# drive.net
KiCad netlist of a schematic drawn in EAGLE
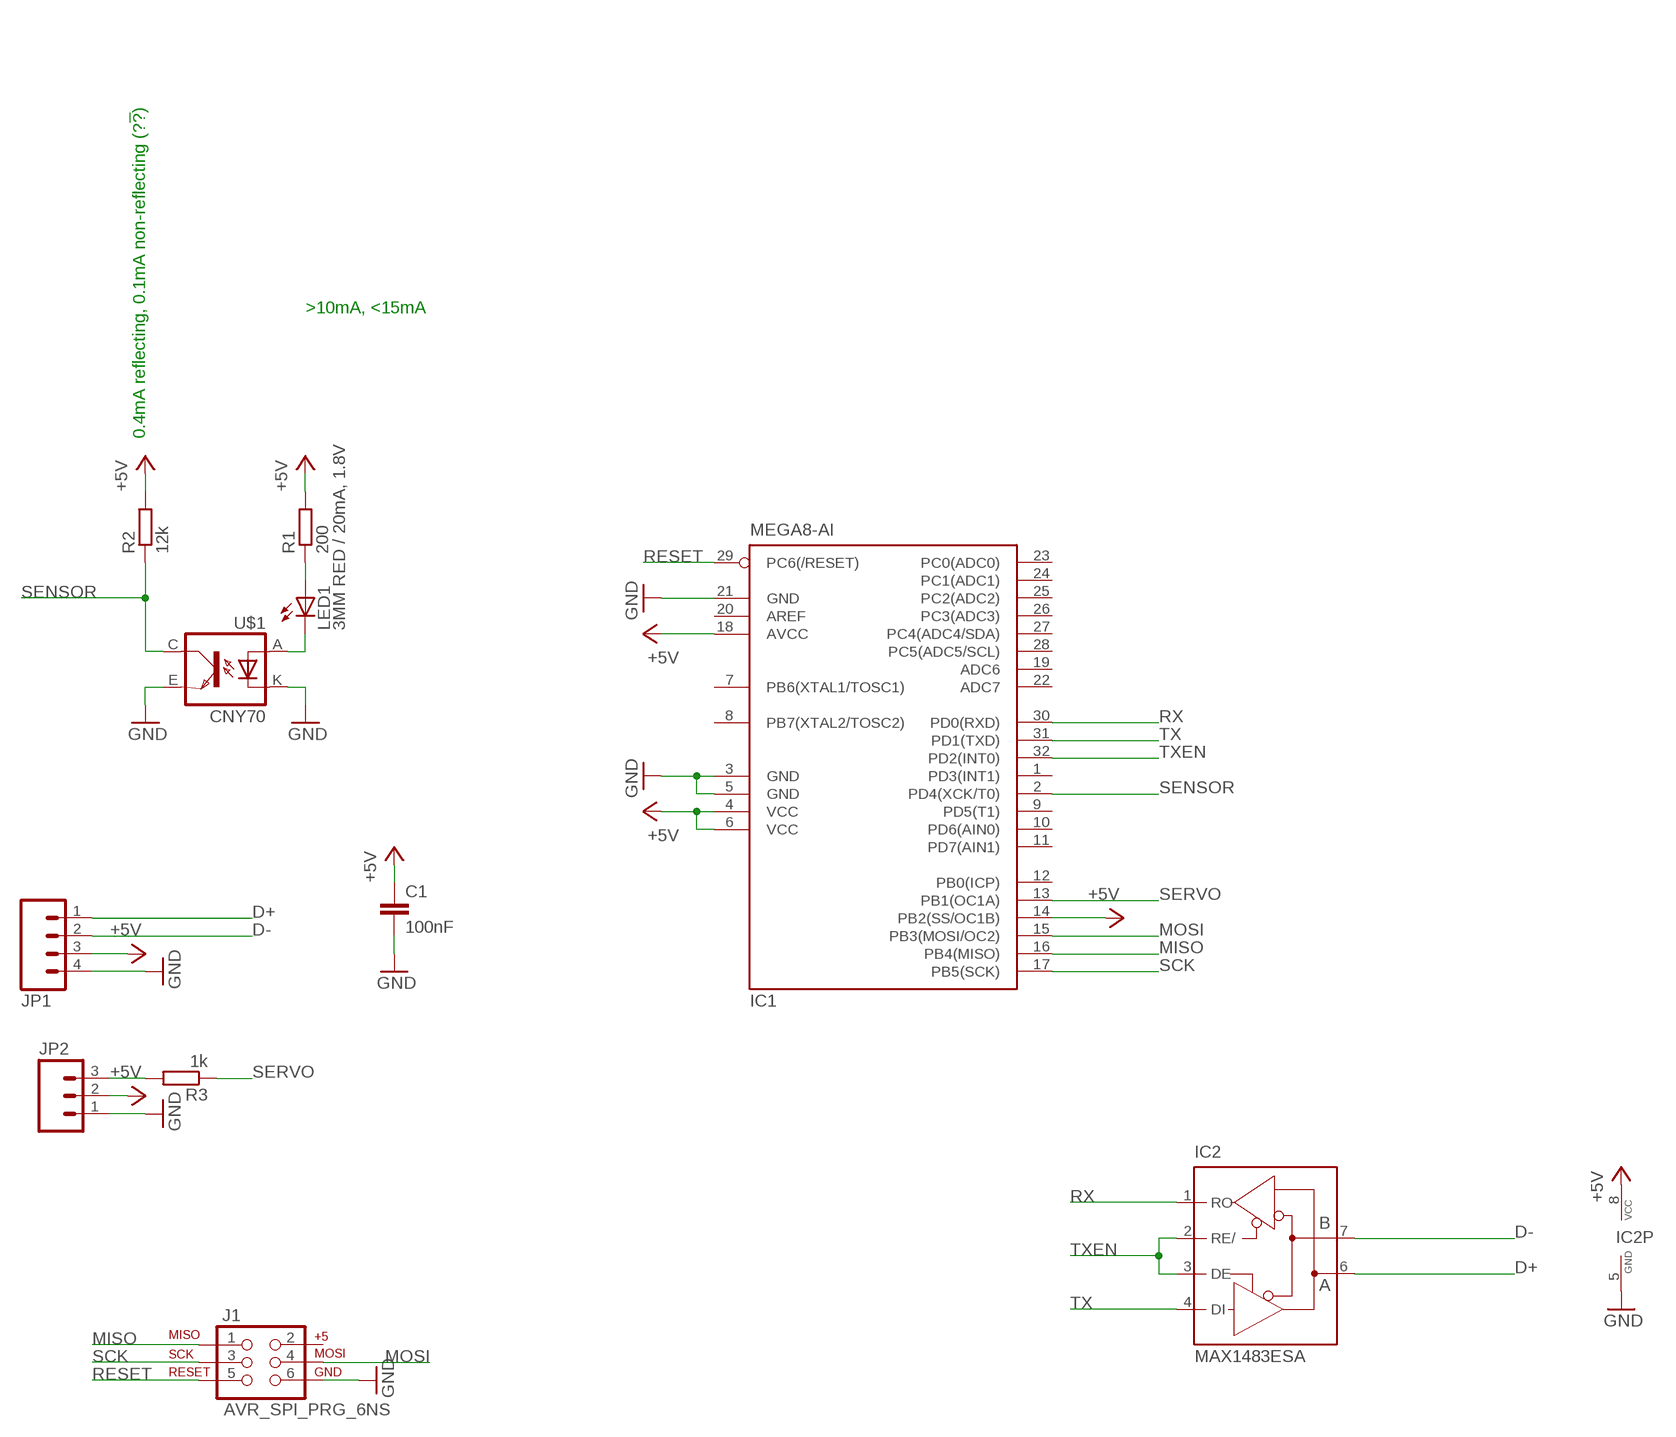
[diagram p0: schematic, sheet 1]

(export (version "E")
  (design (tool "Eeschema 10.0.6"))
  (components
    (comp (ref "C1")
      (value "100nF")
      (footprint "eagle-import:C0805")
      (libsource (lib "eagle-import") (part "C-EUC0805"))
    )
    (comp (ref "IC1")
      (value "MEGA8-AI")
      (footprint "eagle-import:TQFP32-08")
      (fields (field (name "MPN") "ATMEGA8-16AU"))
      (libsource (lib "eagle-import") (part "MEGA8-AI"))
    )
    (comp (ref "IC2")
      (value "MAX1483ESA")
      (footprint "eagle-import:SO08")
      (fields (field (name "MF") "MAXIM") (field (name "MPN") "MAX481CSA"))
      (libsource (lib "eagle-import") (part "MAX481CSA"))
    )
    (comp (ref "J1")
      (value "AVR_SPI_PRG_6NS")
      (footprint "eagle-import:2X3-NS")
      (libsource (lib "eagle-import") (part "AVR_SPI_PRG_6NS"))
    )
    (comp (ref "JP1")
      (value "M04POLAR")
      (footprint "eagle-import:MOLEX-1X4")
      (libsource (lib "eagle-import") (part "M04POLAR"))
    )
    (comp (ref "JP2")
      (value "M03PTH")
      (footprint "eagle-import:1X03")
      (libsource (lib "eagle-import") (part "M03PTH"))
    )
    (comp (ref "LED1")
      (value "3MM RED / 20mA, 1.8V")
      (footprint "eagle-import:LED3MM")
      (libsource (lib "eagle-import") (part "LED3MM"))
    )
    (comp (ref "R1")
      (value "200")
      (footprint "eagle-import:R0805")
      (libsource (lib "eagle-import") (part "R-EU_R0805"))
    )
    (comp (ref "R2")
      (value "12k")
      (footprint "eagle-import:R0805")
      (libsource (lib "eagle-import") (part "R-EU_R0805"))
    )
    (comp (ref "R3")
      (value "1k")
      (footprint "eagle-import:R0805")
      (libsource (lib "eagle-import") (part "R-EU_R0805"))
    )
    (comp (ref "U$1")
      (value "CNY70")
      (footprint "eagle-import:4")
      (libsource (lib "eagle-import") (part "CNY70"))
    )
  )
  (nets
    (net (code "1") (name "+5V") (class "Default")
      (node (ref "C1") (pin "1") (pinfunction "1_1") (pintype "passive"))
      (node (ref "IC1") (pin "14") (pinfunction "PB2(SS/OC1B)_14") (pintype "bidirectional"))
      (node (ref "IC1") (pin "18") (pinfunction "AVCC_18") (pintype "power_in"))
      (node (ref "IC1") (pin "4") (pinfunction "VCC_4") (pintype "power_in"))
      (node (ref "IC1") (pin "6") (pinfunction "VCC_6") (pintype "power_in"))
      (node (ref "IC2") (pin "8") (pinfunction "VCC_8") (pintype "power_in"))
      (node (ref "JP1") (pin "3") (pinfunction "3_3") (pintype "passive"))
      (node (ref "JP2") (pin "2") (pinfunction "2_2") (pintype "passive"))
      (node (ref "R1") (pin "2") (pinfunction "2_2") (pintype "passive"))
      (node (ref "R2") (pin "2") (pinfunction "2_2") (pintype "passive"))
    )
    (net (code "2") (name "/D+") (class "Default")
      (node (ref "IC2") (pin "6") (pinfunction "A_6") (pintype "passive"))
      (node (ref "JP1") (pin "1") (pinfunction "1_1") (pintype "passive"))
    )
    (net (code "3") (name "/D-") (class "Default")
      (node (ref "IC2") (pin "7") (pinfunction "B_7") (pintype "passive"))
      (node (ref "JP1") (pin "2") (pinfunction "2_2") (pintype "passive"))
    )
    (net (code "4") (name "/MISO") (class "Default")
      (node (ref "IC1") (pin "16") (pinfunction "PB4(MISO)_16") (pintype "bidirectional"))
      (node (ref "J1") (pin "1") (pinfunction "1_1") (pintype "passive"))
    )
    (net (code "5") (name "/MOSI") (class "Default")
      (node (ref "IC1") (pin "15") (pinfunction "PB3(MOSI/OC2)_15") (pintype "bidirectional"))
      (node (ref "J1") (pin "4") (pinfunction "4_4") (pintype "passive"))
    )
    (net (code "6") (name "/RESET") (class "Default")
      (node (ref "IC1") (pin "29") (pinfunction "PC6(/RESET)_29") (pintype "bidirectional"))
      (node (ref "J1") (pin "5") (pinfunction "5_5") (pintype "passive"))
    )
    (net (code "7") (name "/RX") (class "Default")
      (node (ref "IC1") (pin "30") (pinfunction "PD0(RXD)_30") (pintype "bidirectional"))
      (node (ref "IC2") (pin "1") (pinfunction "RO_1") (pintype "output"))
    )
    (net (code "8") (name "/SCK") (class "Default")
      (node (ref "IC1") (pin "17") (pinfunction "PB5(SCK)_17") (pintype "bidirectional"))
      (node (ref "J1") (pin "3") (pinfunction "3_3") (pintype "passive"))
    )
    (net (code "9") (name "/SENSOR") (class "Default")
      (node (ref "IC1") (pin "2") (pinfunction "PD4(XCK/T0)_2") (pintype "bidirectional"))
      (node (ref "R2") (pin "1") (pinfunction "1_1") (pintype "passive"))
      (node (ref "U$1") (pin "C") (pinfunction "COL_C") (pintype "passive"))
    )
    (net (code "10") (name "/SERVO") (class "Default")
      (node (ref "IC1") (pin "13") (pinfunction "PB1(OC1A)_13") (pintype "bidirectional"))
      (node (ref "R3") (pin "1") (pinfunction "1_1") (pintype "passive"))
    )
    (net (code "11") (name "/TX") (class "Default")
      (node (ref "IC1") (pin "31") (pinfunction "PD1(TXD)_31") (pintype "bidirectional"))
      (node (ref "IC2") (pin "4") (pinfunction "DI_4") (pintype "input"))
    )
    (net (code "12") (name "/TXEN") (class "Default")
      (node (ref "IC1") (pin "32") (pinfunction "PD2(INT0)_32") (pintype "bidirectional"))
      (node (ref "IC2") (pin "2") (pinfunction "RE/_2") (pintype "input"))
      (node (ref "IC2") (pin "3") (pinfunction "DE_3") (pintype "input"))
    )
    (net (code "13") (name "GND") (class "Default")
      (node (ref "C1") (pin "2") (pinfunction "2_2") (pintype "passive"))
      (node (ref "IC1") (pin "21") (pinfunction "GND_21") (pintype "power_in"))
      (node (ref "IC1") (pin "3") (pinfunction "GND_3") (pintype "power_in"))
      (node (ref "IC1") (pin "5") (pinfunction "GND_5") (pintype "power_in"))
      (node (ref "IC2") (pin "5") (pinfunction "GND_5") (pintype "power_in"))
      (node (ref "J1") (pin "6") (pinfunction "6_6") (pintype "passive"))
      (node (ref "JP1") (pin "4") (pinfunction "4_4") (pintype "passive"))
      (node (ref "JP2") (pin "1") (pinfunction "1_1") (pintype "passive"))
      (node (ref "U$1") (pin "E") (pinfunction "EMI_E") (pintype "passive"))
      (node (ref "U$1") (pin "K") (pinfunction "C_K") (pintype "passive"))
    )
    (net (code "14") (name "Net-(JP2-Pad3)") (class "Default")
      (node (ref "JP2") (pin "3") (pinfunction "3_3") (pintype "passive"))
      (node (ref "R3") (pin "2") (pinfunction "2_2") (pintype "passive"))
    )
    (net (code "15") (name "Net-(LED1-C)") (class "Default")
      (node (ref "LED1") (pin "K") (pinfunction "C_K") (pintype "passive"))
      (node (ref "U$1") (pin "A") (pinfunction "A_A") (pintype "passive"))
    )
    (net (code "16") (name "Net-(LED1-PadA)") (class "Default")
      (node (ref "LED1") (pin "A") (pinfunction "A_A") (pintype "passive"))
      (node (ref "R1") (pin "1") (pinfunction "1_1") (pintype "passive"))
    )
    (net (code "17") (name "unconnected-(IC1-ADC6-Pad19)") (class "Default")
      (node (ref "IC1") (pin "19") (pinfunction "ADC6_19") (pintype "bidirectional"))
    )
    (net (code "18") (name "unconnected-(IC1-ADC7-Pad22)") (class "Default")
      (node (ref "IC1") (pin "22") (pinfunction "ADC7_22") (pintype "bidirectional"))
    )
    (net (code "19") (name "unconnected-(IC1-AREF-Pad20)") (class "Default")
      (node (ref "IC1") (pin "20") (pinfunction "AREF_20") (pintype "passive"))
    )
    (net (code "20") (name "unconnected-(IC1-PB0(ICP)-Pad12)") (class "Default")
      (node (ref "IC1") (pin "12") (pinfunction "PB0(ICP)_12") (pintype "bidirectional"))
    )
    (net (code "21") (name "unconnected-(IC1-PB6(XTAL1{slash}TOSC1)-Pad7)") (class "Default")
      (node (ref "IC1") (pin "7") (pinfunction "PB6(XTAL1/TOSC1)_7") (pintype "bidirectional"))
    )
    (net (code "22") (name "unconnected-(IC1-PB7(XTAL2{slash}TOSC2)-Pad8)") (class "Default")
      (node (ref "IC1") (pin "8") (pinfunction "PB7(XTAL2/TOSC2)_8") (pintype "bidirectional"))
    )
    (net (code "23") (name "unconnected-(IC1-PC0(ADC0)-Pad23)") (class "Default")
      (node (ref "IC1") (pin "23") (pinfunction "PC0(ADC0)_23") (pintype "bidirectional"))
    )
    (net (code "24") (name "unconnected-(IC1-PC1(ADC1)-Pad24)") (class "Default")
      (node (ref "IC1") (pin "24") (pinfunction "PC1(ADC1)_24") (pintype "bidirectional"))
    )
    (net (code "25") (name "unconnected-(IC1-PC2(ADC2)-Pad25)") (class "Default")
      (node (ref "IC1") (pin "25") (pinfunction "PC2(ADC2)_25") (pintype "bidirectional"))
    )
    (net (code "26") (name "unconnected-(IC1-PC3(ADC3)-Pad26)") (class "Default")
      (node (ref "IC1") (pin "26") (pinfunction "PC3(ADC3)_26") (pintype "bidirectional"))
    )
    (net (code "27") (name "unconnected-(IC1-PC4(ADC4{slash}SDA)-Pad27)") (class "Default")
      (node (ref "IC1") (pin "27") (pinfunction "PC4(ADC4/SDA)_27") (pintype "bidirectional"))
    )
    (net (code "28") (name "unconnected-(IC1-PC5(ADC5{slash}SCL)-Pad28)") (class "Default")
      (node (ref "IC1") (pin "28") (pinfunction "PC5(ADC5/SCL)_28") (pintype "bidirectional"))
    )
    (net (code "29") (name "unconnected-(IC1-PD3(INT1)-Pad1)") (class "Default")
      (node (ref "IC1") (pin "1") (pinfunction "PD3(INT1)_1") (pintype "bidirectional"))
    )
    (net (code "30") (name "unconnected-(IC1-PD5(T1)-Pad9)") (class "Default")
      (node (ref "IC1") (pin "9") (pinfunction "PD5(T1)_9") (pintype "bidirectional"))
    )
    (net (code "31") (name "unconnected-(IC1-PD6(AIN0)-Pad10)") (class "Default")
      (node (ref "IC1") (pin "10") (pinfunction "PD6(AIN0)_10") (pintype "bidirectional"))
    )
    (net (code "32") (name "unconnected-(IC1-PD7(AIN1)-Pad11)") (class "Default")
      (node (ref "IC1") (pin "11") (pinfunction "PD7(AIN1)_11") (pintype "bidirectional"))
    )
    (net (code "33") (name "unconnected-(J1-Pad2)") (class "Default")
      (node (ref "J1") (pin "2") (pinfunction "2_2") (pintype "passive"))
    )
  )
)
